# GenRF_R00.net
KiCad netlist of a schematic drawn in Altium Designer
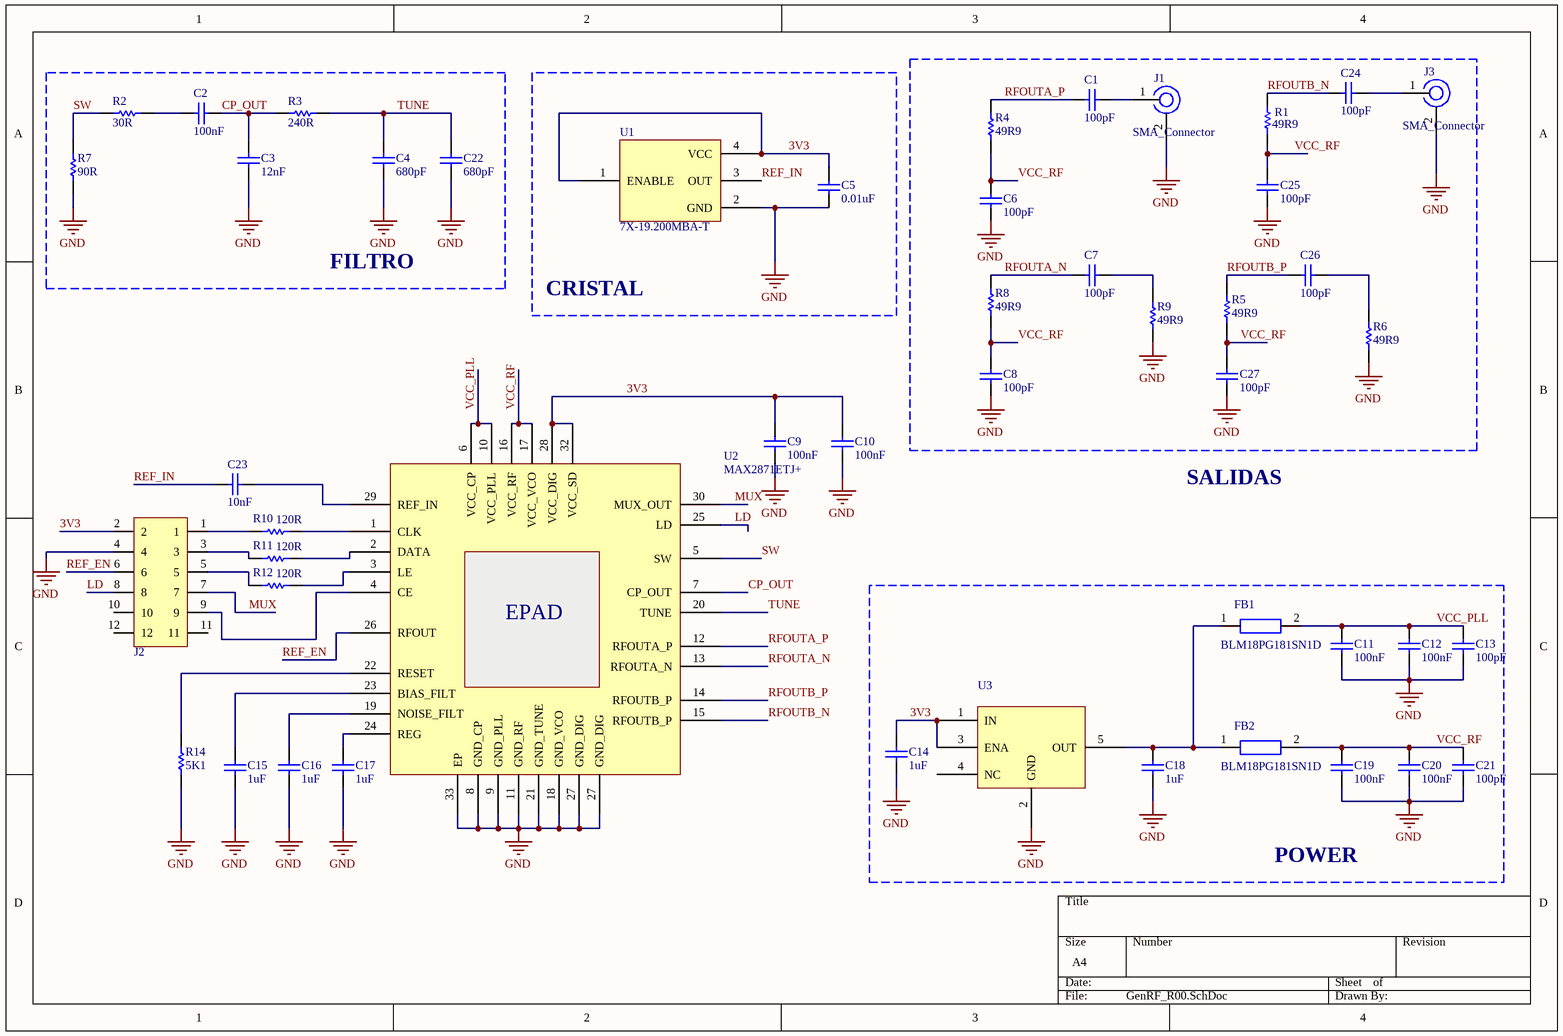
[diagram p0: GenRF_R00.SchDoc]

(export (version "E")
  (design (tool "Eeschema 10.0.6"))
  (components
    (comp (ref "C1")
      (value "100pF")
      (footprint "C_0603")
      (description "Capacitor")
      (libsource (lib "Simulation Generic Components") (part "Capacitor"))
    )
    (comp (ref "C2")
      (value "100nF")
      (footprint "C_0805")
      (description "Capacitor")
      (libsource (lib "Simulation Generic Components") (part "Capacitor"))
    )
    (comp (ref "C3")
      (value "12nF")
      (footprint "C_0805")
      (description "Capacitor")
      (libsource (lib "Simulation Generic Components") (part "Capacitor"))
    )
    (comp (ref "C4")
      (value "680pF")
      (footprint "C_0805")
      (description "Capacitor")
      (libsource (lib "Simulation Generic Components") (part "Capacitor"))
    )
    (comp (ref "C5")
      (value "0.01uF")
      (footprint "C_0805")
      (description "Capacitor")
      (libsource (lib "Simulation Generic Components") (part "Capacitor"))
    )
    (comp (ref "C6")
      (value "100pF")
      (footprint "C_0805")
      (description "Capacitor")
      (libsource (lib "Simulation Generic Components") (part "Capacitor"))
    )
    (comp (ref "C7")
      (value "100pF")
      (footprint "C_0603")
      (description "Capacitor")
      (libsource (lib "Simulation Generic Components") (part "Capacitor"))
    )
    (comp (ref "C8")
      (value "100pF")
      (footprint "C_0805")
      (description "Capacitor")
      (libsource (lib "Simulation Generic Components") (part "Capacitor"))
    )
    (comp (ref "C9")
      (value "100nF")
      (footprint "C_0805")
      (description "Capacitor")
      (libsource (lib "Simulation Generic Components") (part "Capacitor"))
    )
    (comp (ref "C10")
      (value "100nF")
      (footprint "C_0805")
      (description "Capacitor")
      (libsource (lib "Simulation Generic Components") (part "Capacitor"))
    )
    (comp (ref "C11")
      (value "100nF")
      (footprint "C_0805")
      (description "Capacitor")
      (libsource (lib "Simulation Generic Components") (part "Capacitor"))
    )
    (comp (ref "C12")
      (value "100nF")
      (footprint "C_0805")
      (description "Capacitor")
      (libsource (lib "Simulation Generic Components") (part "Capacitor"))
    )
    (comp (ref "C13")
      (value "100pF")
      (footprint "C_0805")
      (description "Capacitor")
      (libsource (lib "Simulation Generic Components") (part "Capacitor"))
    )
    (comp (ref "C14")
      (value "1uF")
      (footprint "C_0805")
      (description "Capacitor")
      (libsource (lib "Simulation Generic Components") (part "Capacitor"))
    )
    (comp (ref "C15")
      (value "1uF")
      (footprint "C_0805")
      (description "Capacitor")
      (libsource (lib "Simulation Generic Components") (part "Capacitor"))
    )
    (comp (ref "C16")
      (value "1uF")
      (footprint "C_0805")
      (description "Capacitor")
      (libsource (lib "Simulation Generic Components") (part "Capacitor"))
    )
    (comp (ref "C17")
      (value "1uF")
      (footprint "C_0805")
      (description "Capacitor")
      (libsource (lib "Simulation Generic Components") (part "Capacitor"))
    )
    (comp (ref "C18")
      (value "1uF")
      (footprint "C_0805")
      (description "Capacitor")
      (libsource (lib "Simulation Generic Components") (part "Capacitor"))
    )
    (comp (ref "C19")
      (value "100nF")
      (footprint "C_0805")
      (description "Capacitor")
      (libsource (lib "Simulation Generic Components") (part "Capacitor"))
    )
    (comp (ref "C20")
      (value "100nF")
      (footprint "C_0805")
      (description "Capacitor")
      (libsource (lib "Simulation Generic Components") (part "Capacitor"))
    )
    (comp (ref "C21")
      (value "100pF")
      (footprint "C_0805")
      (description "Capacitor")
      (libsource (lib "Simulation Generic Components") (part "Capacitor"))
    )
    (comp (ref "C22")
      (value "680pF")
      (footprint "C_0805")
      (description "Capacitor")
      (libsource (lib "Simulation Generic Components") (part "Capacitor"))
    )
    (comp (ref "C23")
      (value "10nF")
      (footprint "C_0805")
      (description "Capacitor")
      (libsource (lib "Simulation Generic Components") (part "Capacitor"))
    )
    (comp (ref "C24")
      (value "100pF")
      (footprint "C_0603")
      (description "Capacitor")
      (libsource (lib "Simulation Generic Components") (part "Capacitor"))
    )
    (comp (ref "C25")
      (value "100pF")
      (footprint "C_0805")
      (description "Capacitor")
      (libsource (lib "Simulation Generic Components") (part "Capacitor"))
    )
    (comp (ref "C26")
      (value "100pF")
      (footprint "C_0603")
      (description "Capacitor")
      (libsource (lib "Simulation Generic Components") (part "Capacitor"))
    )
    (comp (ref "C27")
      (value "100pF")
      (footprint "C_0805")
      (description "Capacitor")
      (libsource (lib "Simulation Generic Components") (part "Capacitor"))
    )
    (comp (ref "FB1")
      (value "BLM18PG181SN1D")
      (footprint "FB_0603")
      (libsource (lib "GenRF_R00") (part "Ferrite Bead"))
    )
    (comp (ref "FB2")
      (value "BLM18PG181SN1D")
      (footprint "FB_0603")
      (libsource (lib "GenRF_R00") (part "Ferrite Bead"))
    )
    (comp (ref "J1")
      (value "SMA_Connector")
      (footprint "SMA_Connector")
      (description "Connector SMA")
      (libsource (lib "SchLib_PocketAnalyzer") (part "SMA_Connector"))
    )
    (comp (ref "J2")
      (value "Tira de pines de 12")
      (footprint "Header_M_2x6_0.1\"")
      (libsource (lib "GenRF_R00") (part "Headpin 10"))
    )
    (comp (ref "J3")
      (value "SMA_Connector")
      (footprint "SMA_Connector")
      (description "Connector SMA")
      (libsource (lib "SchLib_PocketAnalyzer") (part "SMA_Connector"))
    )
    (comp (ref "R1")
      (value "49R9")
      (footprint "R_0603")
      (description "Resistor")
      (libsource (lib "Simulation Generic Components") (part "Resistor"))
    )
    (comp (ref "R2")
      (value "30R")
      (footprint "R_0805")
      (description "Resistor")
      (libsource (lib "Simulation Generic Components") (part "Resistor"))
    )
    (comp (ref "R3")
      (value "240R")
      (footprint "R_0805")
      (description "Resistor")
      (libsource (lib "Simulation Generic Components") (part "Resistor"))
    )
    (comp (ref "R4")
      (value "49R9")
      (footprint "R_0603")
      (description "Resistor")
      (libsource (lib "Simulation Generic Components") (part "Resistor"))
    )
    (comp (ref "R5")
      (value "49R9")
      (footprint "R_0603")
      (description "Resistor")
      (libsource (lib "Simulation Generic Components") (part "Resistor"))
    )
    (comp (ref "R6")
      (value "49R9")
      (footprint "R_0603")
      (description "Resistor")
      (libsource (lib "Simulation Generic Components") (part "Resistor"))
    )
    (comp (ref "R7")
      (value "90R")
      (footprint "R_0805")
      (description "Resistor")
      (libsource (lib "Simulation Generic Components") (part "Resistor"))
    )
    (comp (ref "R8")
      (value "49R9")
      (footprint "R_0603")
      (description "Resistor")
      (libsource (lib "Simulation Generic Components") (part "Resistor"))
    )
    (comp (ref "R9")
      (value "49R9")
      (footprint "R_0603")
      (description "Resistor")
      (libsource (lib "Simulation Generic Components") (part "Resistor"))
    )
    (comp (ref "R10")
      (value "120R")
      (footprint "R_0805")
      (description "Resistor")
      (libsource (lib "Simulation Generic Components") (part "Resistor"))
    )
    (comp (ref "R11")
      (value "120R")
      (footprint "R_0805")
      (description "Resistor")
      (libsource (lib "Simulation Generic Components") (part "Resistor"))
    )
    (comp (ref "R12")
      (value "120R")
      (footprint "R_0805")
      (description "Resistor")
      (libsource (lib "Simulation Generic Components") (part "Resistor"))
    )
    (comp (ref "R14")
      (value "5K1")
      (footprint "R_0805")
      (description "Resistor")
      (libsource (lib "Simulation Generic Components") (part "Resistor"))
    )
    (comp (ref "U1")
      (value "7X-19.200MBA-T")
      (footprint "XTAL")
      (description "XTAL OSC XO 19.2000MHZ CMOS SMD")
      (libsource (lib "GenRF_R00") (part "7X-19.200MBA-T"))
    )
    (comp (ref "U2")
      (value "MAX2871ETJ+")
      (footprint "MAX2870ETJ+")
      (libsource (lib "GenRF_R00") (part "MAX2871ETJ+"))
    )
    (comp (ref "U3")
      (value "LP5907QMFX-3.3")
      (footprint "TSOP")
      (description "IC REG LINEAR 3.3V 250MA SOT23-5")
      (libsource (lib "GenRF_R00") (part "LP5907QMFX-3.3"))
    )
  )
  (nets
    (net (code "1") (name "/3V3") (class "Default")
      (node (ref "C10") (pin "2") (pinfunction "2_2") (pintype "passive"))
      (node (ref "C14") (pin "2") (pinfunction "2_2") (pintype "passive"))
      (node (ref "C5") (pin "1") (pinfunction "1_1") (pintype "passive"))
      (node (ref "C9") (pin "2") (pinfunction "2_2") (pintype "passive"))
      (node (ref "J2") (pin "2") (pinfunction "2_2") (pintype "passive"))
      (node (ref "U1") (pin "1") (pinfunction "ENABLE_1") (pintype "passive"))
      (node (ref "U1") (pin "4") (pinfunction "VCC_4") (pintype "passive"))
      (node (ref "U2") (pin "28") (pinfunction "VCC_DIG_28") (pintype "passive"))
      (node (ref "U2") (pin "32") (pinfunction "VCC_SD_32") (pintype "passive"))
      (node (ref "U3") (pin "1") (pinfunction "IN_1") (pintype "passive"))
      (node (ref "U3") (pin "3") (pinfunction "ENA_3") (pintype "passive"))
    )
    (net (code "2") (name "/CP_OUT") (class "Default")
      (node (ref "C2") (pin "1") (pinfunction "1_1") (pintype "passive"))
      (node (ref "C3") (pin "2") (pinfunction "2_2") (pintype "passive"))
      (node (ref "R3") (pin "2") (pinfunction "2_2") (pintype "passive"))
      (node (ref "U2") (pin "7") (pinfunction "CP_OUT_7") (pintype "passive"))
    )
    (net (code "3") (name "/LD") (class "Default")
      (node (ref "J2") (pin "8") (pinfunction "8_8") (pintype "passive"))
      (node (ref "U2") (pin "25") (pinfunction "LD_25") (pintype "passive"))
    )
    (net (code "4") (name "/MUX") (class "Default")
      (node (ref "J2") (pin "7") (pinfunction "7_7") (pintype "passive"))
      (node (ref "U2") (pin "30") (pinfunction "MUX_OUT_30") (pintype "passive"))
    )
    (net (code "5") (name "/REF_EN") (class "Default")
      (node (ref "J2") (pin "6") (pinfunction "6_6") (pintype "passive"))
      (node (ref "U2") (pin "26") (pinfunction "RFOUT_26") (pintype "passive"))
    )
    (net (code "6") (name "/REF_IN") (class "Default")
      (node (ref "C23") (pin "2") (pinfunction "2_2") (pintype "passive"))
      (node (ref "U1") (pin "3") (pinfunction "OUT_3") (pintype "passive"))
    )
    (net (code "7") (name "/RFOUTA_N") (class "Default")
      (node (ref "C7") (pin "1") (pinfunction "1_1") (pintype "passive"))
      (node (ref "R8") (pin "2") (pinfunction "2_2") (pintype "passive"))
      (node (ref "U2") (pin "13") (pinfunction "RFOUTA_N_13") (pintype "passive"))
    )
    (net (code "8") (name "/RFOUTA_P") (class "Default")
      (node (ref "C1") (pin "1") (pinfunction "1_1") (pintype "passive"))
      (node (ref "R4") (pin "2") (pinfunction "2_2") (pintype "passive"))
      (node (ref "U2") (pin "12") (pinfunction "RFOUTA_P_12") (pintype "passive"))
    )
    (net (code "9") (name "/RFOUTB_N") (class "Default")
      (node (ref "C24") (pin "1") (pinfunction "1_1") (pintype "passive"))
      (node (ref "R1") (pin "2") (pinfunction "2_2") (pintype "passive"))
      (node (ref "U2") (pin "15") (pinfunction "RFOUTB_P_15") (pintype "passive"))
    )
    (net (code "10") (name "/RFOUTB_P") (class "Default")
      (node (ref "C26") (pin "1") (pinfunction "1_1") (pintype "passive"))
      (node (ref "R5") (pin "1") (pinfunction "1_1") (pintype "passive"))
      (node (ref "U2") (pin "14") (pinfunction "RFOUTB_P_14") (pintype "passive"))
    )
    (net (code "11") (name "/SW") (class "Default")
      (node (ref "R2") (pin "1") (pinfunction "1_1") (pintype "passive"))
      (node (ref "R7") (pin "1") (pinfunction "1_1") (pintype "passive"))
      (node (ref "U2") (pin "5") (pinfunction "SW_5") (pintype "passive"))
    )
    (net (code "12") (name "/TUNE") (class "Default")
      (node (ref "C22") (pin "2") (pinfunction "2_2") (pintype "passive"))
      (node (ref "C4") (pin "2") (pinfunction "2_2") (pintype "passive"))
      (node (ref "R3") (pin "1") (pinfunction "1_1") (pintype "passive"))
      (node (ref "U2") (pin "20") (pinfunction "TUNE_20") (pintype "passive"))
    )
    (net (code "13") (name "/VCC_PLL") (class "Default")
      (node (ref "C11") (pin "2") (pinfunction "2_2") (pintype "passive"))
      (node (ref "C12") (pin "2") (pinfunction "2_2") (pintype "passive"))
      (node (ref "C13") (pin "2") (pinfunction "2_2") (pintype "passive"))
      (node (ref "FB1") (pin "2") (pintype "passive"))
      (node (ref "U2") (pin "10") (pinfunction "VCC_PLL_10") (pintype "passive"))
      (node (ref "U2") (pin "6") (pinfunction "VCC_CP_6") (pintype "passive"))
    )
    (net (code "14") (name "/VCC_RF") (class "Default")
      (node (ref "C19") (pin "2") (pinfunction "2_2") (pintype "passive"))
      (node (ref "C20") (pin "2") (pinfunction "2_2") (pintype "passive"))
      (node (ref "C21") (pin "2") (pinfunction "2_2") (pintype "passive"))
      (node (ref "C25") (pin "1") (pinfunction "1_1") (pintype "passive"))
      (node (ref "C27") (pin "1") (pinfunction "1_1") (pintype "passive"))
      (node (ref "C6") (pin "1") (pinfunction "1_1") (pintype "passive"))
      (node (ref "C8") (pin "1") (pinfunction "1_1") (pintype "passive"))
      (node (ref "FB2") (pin "2") (pintype "passive"))
      (node (ref "R1") (pin "1") (pinfunction "1_1") (pintype "passive"))
      (node (ref "R4") (pin "1") (pinfunction "1_1") (pintype "passive"))
      (node (ref "R5") (pin "2") (pinfunction "2_2") (pintype "passive"))
      (node (ref "R8") (pin "1") (pinfunction "1_1") (pintype "passive"))
      (node (ref "U2") (pin "16") (pinfunction "VCC_RF_16") (pintype "passive"))
      (node (ref "U2") (pin "17") (pinfunction "VCC_VCO_17") (pintype "passive"))
    )
    (net (code "15") (name "GND") (class "Default")
      (node (ref "C10") (pin "1") (pinfunction "1_1") (pintype "passive"))
      (node (ref "C11") (pin "1") (pinfunction "1_1") (pintype "passive"))
      (node (ref "C12") (pin "1") (pinfunction "1_1") (pintype "passive"))
      (node (ref "C13") (pin "1") (pinfunction "1_1") (pintype "passive"))
      (node (ref "C14") (pin "1") (pinfunction "1_1") (pintype "passive"))
      (node (ref "C15") (pin "1") (pinfunction "1_1") (pintype "passive"))
      (node (ref "C16") (pin "1") (pinfunction "1_1") (pintype "passive"))
      (node (ref "C17") (pin "1") (pinfunction "1_1") (pintype "passive"))
      (node (ref "C18") (pin "1") (pinfunction "1_1") (pintype "passive"))
      (node (ref "C19") (pin "1") (pinfunction "1_1") (pintype "passive"))
      (node (ref "C20") (pin "1") (pinfunction "1_1") (pintype "passive"))
      (node (ref "C21") (pin "1") (pinfunction "1_1") (pintype "passive"))
      (node (ref "C22") (pin "1") (pinfunction "1_1") (pintype "passive"))
      (node (ref "C25") (pin "2") (pinfunction "2_2") (pintype "passive"))
      (node (ref "C27") (pin "2") (pinfunction "2_2") (pintype "passive"))
      (node (ref "C3") (pin "1") (pinfunction "1_1") (pintype "passive"))
      (node (ref "C4") (pin "1") (pinfunction "1_1") (pintype "passive"))
      (node (ref "C5") (pin "2") (pinfunction "2_2") (pintype "passive"))
      (node (ref "C6") (pin "2") (pinfunction "2_2") (pintype "passive"))
      (node (ref "C8") (pin "2") (pinfunction "2_2") (pintype "passive"))
      (node (ref "C9") (pin "1") (pinfunction "1_1") (pintype "passive"))
      (node (ref "J1") (pin "2") (pinfunction "2_2") (pintype "passive"))
      (node (ref "J2") (pin "4") (pinfunction "4_4") (pintype "passive"))
      (node (ref "J3") (pin "2") (pinfunction "2_2") (pintype "passive"))
      (node (ref "R14") (pin "1") (pinfunction "1_1") (pintype "passive"))
      (node (ref "R6") (pin "2") (pinfunction "2_2") (pintype "passive"))
      (node (ref "R7") (pin "2") (pinfunction "2_2") (pintype "passive"))
      (node (ref "R9") (pin "2") (pinfunction "2_2") (pintype "passive"))
      (node (ref "U1") (pin "2") (pinfunction "GND_2") (pintype "passive"))
      (node (ref "U2") (pin "11") (pinfunction "GND_RF_11") (pintype "passive"))
      (node (ref "U2") (pin "18") (pinfunction "GND_VCO_18") (pintype "passive"))
      (node (ref "U2") (pin "21") (pinfunction "GND_TUNE_21") (pintype "passive"))
      (node (ref "U2") (pin "27") (pinfunction "GND_DIG_27") (pintype "passive"))
      (node (ref "U2") (pin "33") (pinfunction "EP_33") (pintype "passive"))
      (node (ref "U2") (pin "8") (pinfunction "GND_CP_8") (pintype "passive"))
      (node (ref "U2") (pin "9") (pinfunction "GND_PLL_9") (pintype "passive"))
      (node (ref "U3") (pin "2") (pinfunction "GND_2") (pintype "passive"))
    )
    (net (code "16") (name "Net-(C1-Pad2)") (class "Default")
      (node (ref "C1") (pin "2") (pinfunction "2_2") (pintype "passive"))
      (node (ref "J1") (pin "1") (pinfunction "1_1") (pintype "passive"))
    )
    (net (code "17") (name "Net-(C2-Pad2)") (class "Default")
      (node (ref "C2") (pin "2") (pinfunction "2_2") (pintype "passive"))
      (node (ref "R2") (pin "2") (pinfunction "2_2") (pintype "passive"))
    )
    (net (code "18") (name "Net-(C7-Pad2)") (class "Default")
      (node (ref "C7") (pin "2") (pinfunction "2_2") (pintype "passive"))
      (node (ref "R9") (pin "1") (pinfunction "1_1") (pintype "passive"))
    )
    (net (code "19") (name "Net-(C24-Pad2)") (class "Default")
      (node (ref "C24") (pin "2") (pinfunction "2_2") (pintype "passive"))
      (node (ref "J3") (pin "1") (pinfunction "1_1") (pintype "passive"))
    )
    (net (code "20") (name "Net-(C26-Pad2)") (class "Default")
      (node (ref "C26") (pin "2") (pinfunction "2_2") (pintype "passive"))
      (node (ref "R6") (pin "1") (pinfunction "1_1") (pintype "passive"))
    )
    (net (code "21") (name "Net-(J2-Pad1)") (class "Default")
      (node (ref "J2") (pin "1") (pinfunction "1_1") (pintype "passive"))
      (node (ref "R10") (pin "1") (pinfunction "1_1") (pintype "passive"))
    )
    (net (code "22") (name "Net-(J2-Pad3)") (class "Default")
      (node (ref "J2") (pin "3") (pinfunction "3_3") (pintype "passive"))
      (node (ref "R11") (pin "1") (pinfunction "1_1") (pintype "passive"))
    )
    (net (code "23") (name "Net-(J2-Pad5)") (class "Default")
      (node (ref "J2") (pin "5") (pinfunction "5_5") (pintype "passive"))
      (node (ref "R12") (pin "1") (pinfunction "1_1") (pintype "passive"))
    )
    (net (code "24") (name "Net-(U2-BIAS_FILT)") (class "Default")
      (node (ref "C15") (pin "2") (pinfunction "2_2") (pintype "passive"))
      (node (ref "U2") (pin "23") (pinfunction "BIAS_FILT_23") (pintype "passive"))
    )
    (net (code "25") (name "Net-(U2-CE)") (class "Default")
      (node (ref "J2") (pin "9") (pinfunction "9_9") (pintype "passive"))
      (node (ref "U2") (pin "4") (pinfunction "CE_4") (pintype "passive"))
    )
    (net (code "26") (name "Net-(U2-CLK)") (class "Default")
      (node (ref "R10") (pin "2") (pinfunction "2_2") (pintype "passive"))
      (node (ref "U2") (pin "1") (pinfunction "CLK_1") (pintype "passive"))
    )
    (net (code "27") (name "Net-(U2-DATA)") (class "Default")
      (node (ref "R11") (pin "2") (pinfunction "2_2") (pintype "passive"))
      (node (ref "U2") (pin "2") (pinfunction "DATA_2") (pintype "passive"))
    )
    (net (code "28") (name "Net-(U2-LE)") (class "Default")
      (node (ref "R12") (pin "2") (pinfunction "2_2") (pintype "passive"))
      (node (ref "U2") (pin "3") (pinfunction "LE_3") (pintype "passive"))
    )
    (net (code "29") (name "Net-(U2-NOISE_FILT)") (class "Default")
      (node (ref "C16") (pin "2") (pinfunction "2_2") (pintype "passive"))
      (node (ref "U2") (pin "19") (pinfunction "NOISE_FILT_19") (pintype "passive"))
    )
    (net (code "30") (name "Net-(U2-REF_IN)") (class "Default")
      (node (ref "C23") (pin "1") (pinfunction "1_1") (pintype "passive"))
      (node (ref "U2") (pin "29") (pinfunction "REF_IN_29") (pintype "passive"))
    )
    (net (code "31") (name "Net-(U2-REG)") (class "Default")
      (node (ref "C17") (pin "2") (pinfunction "2_2") (pintype "passive"))
      (node (ref "U2") (pin "24") (pinfunction "REG_24") (pintype "passive"))
    )
    (net (code "32") (name "Net-(U2-RESET)") (class "Default")
      (node (ref "R14") (pin "2") (pinfunction "2_2") (pintype "passive"))
      (node (ref "U2") (pin "22") (pinfunction "RESET_22") (pintype "passive"))
    )
    (net (code "33") (name "Net-(U3-OUT)") (class "Default")
      (node (ref "C18") (pin "2") (pinfunction "2_2") (pintype "passive"))
      (node (ref "FB1") (pin "1") (pintype "passive"))
      (node (ref "FB2") (pin "1") (pintype "passive"))
      (node (ref "U3") (pin "5") (pinfunction "OUT_5") (pintype "passive"))
    )
    (net (code "34") (name "unconnected-(J2-Pad10)") (class "Default")
      (node (ref "J2") (pin "10") (pinfunction "10_10") (pintype "passive"))
    )
    (net (code "35") (name "unconnected-(J2-Pad11)") (class "Default")
      (node (ref "J2") (pin "11") (pinfunction "11_11") (pintype "passive"))
    )
    (net (code "36") (name "unconnected-(J2-Pad12)") (class "Default")
      (node (ref "J2") (pin "12") (pinfunction "12_12") (pintype "passive"))
    )
    (net (code "37") (name "unconnected-(U3-NC-Pad4)") (class "Default")
      (node (ref "U3") (pin "4") (pinfunction "NC_4") (pintype "passive"))
    )
  )
)
